# badge_0_0.net
KiCad netlist of a schematic drawn in EAGLE
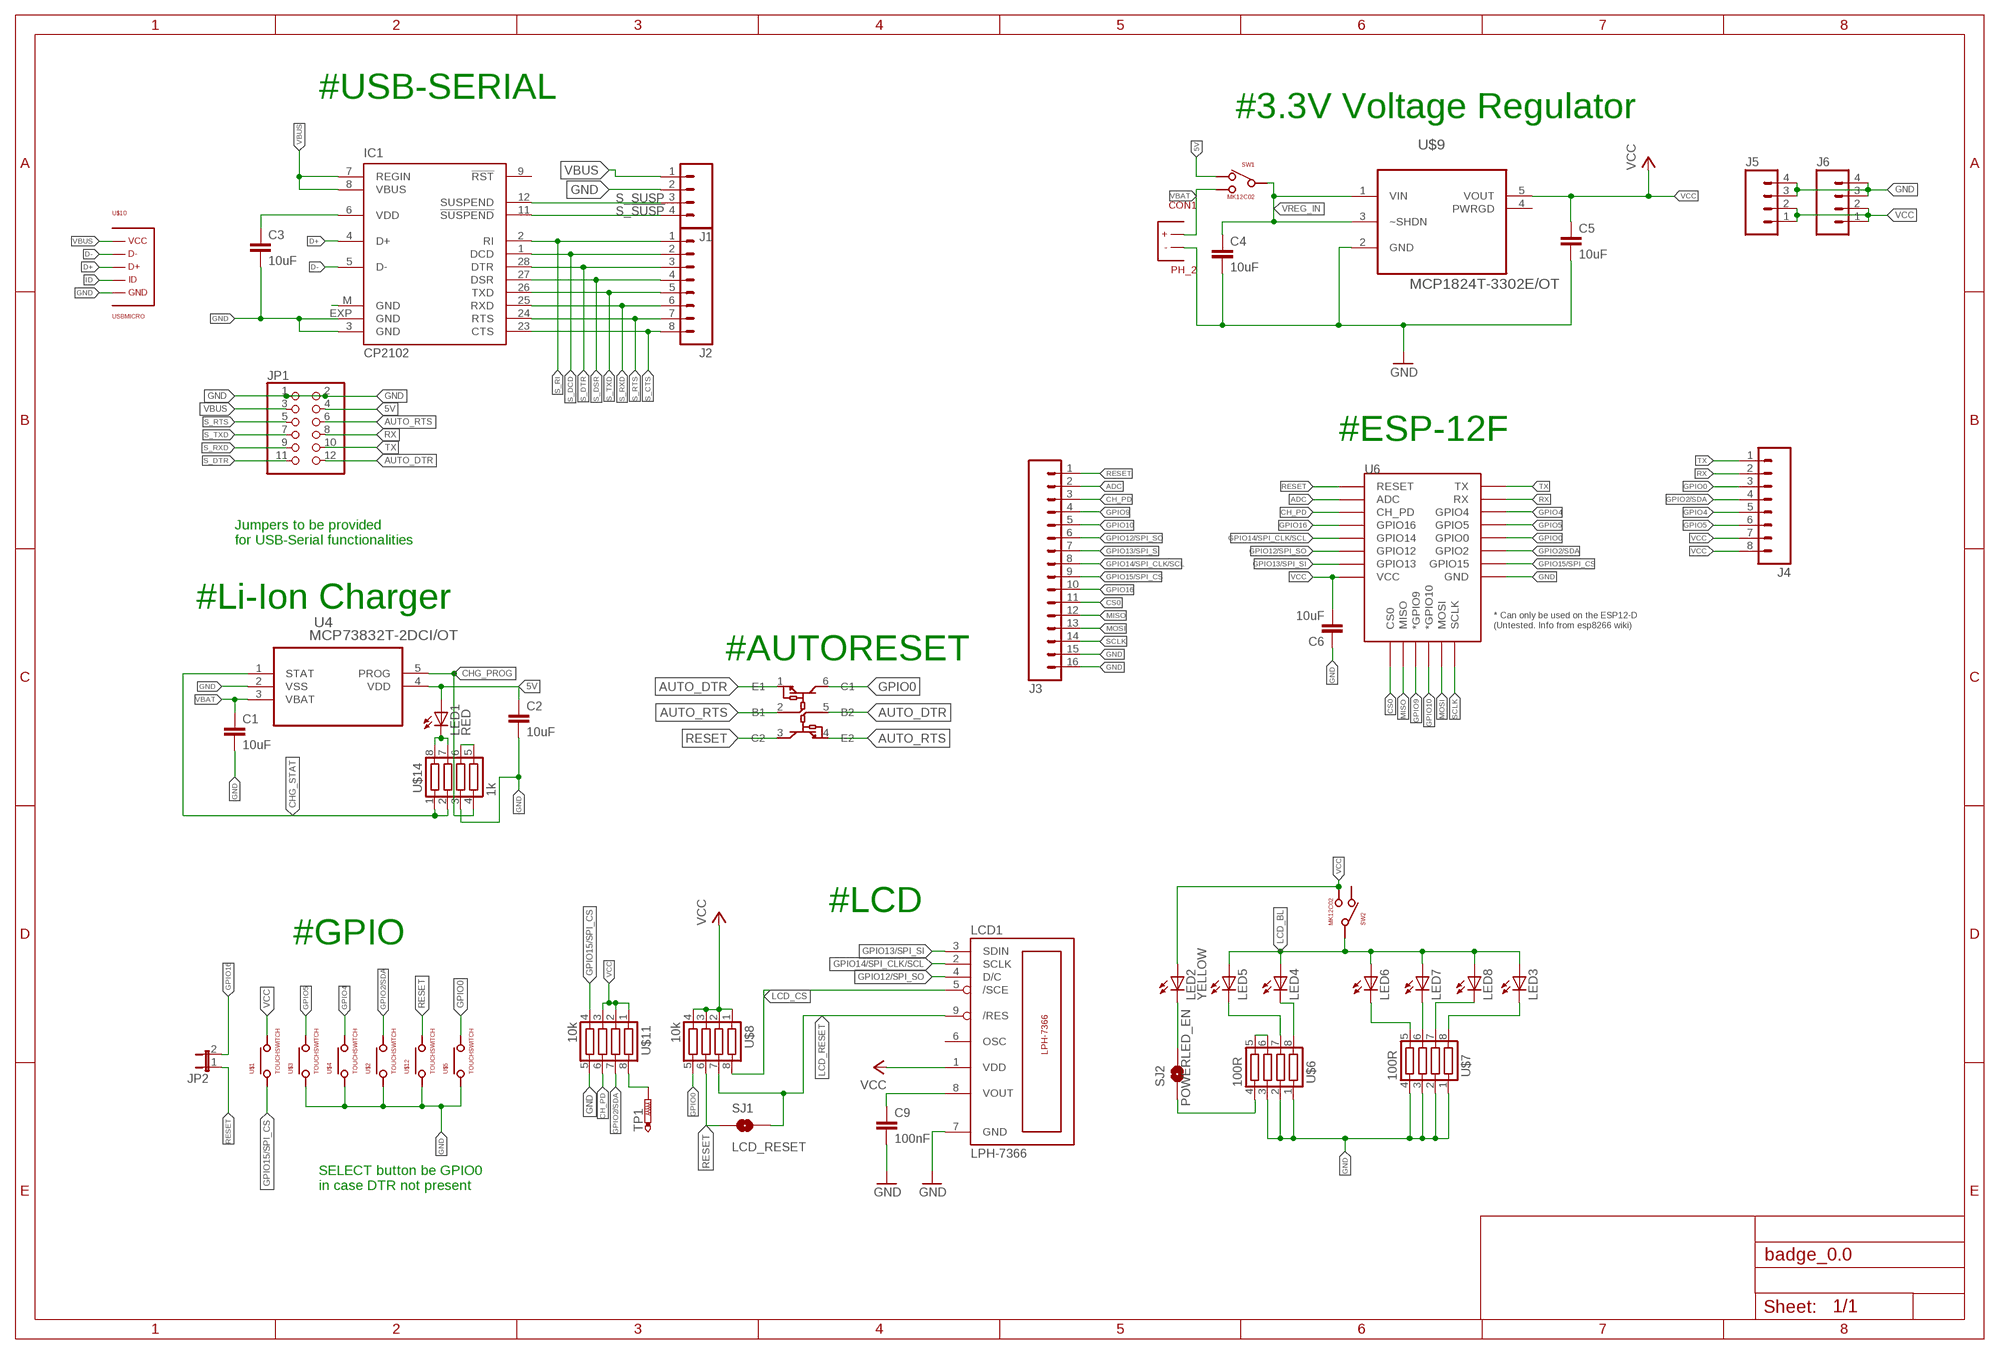
[diagram p0: schematic, sheet 1]

(export (version "E")
  (design (tool "Eeschema 10.0.6"))
  (components
    (comp (ref "C1")
      (value "10uF")
      (footprint "eagle-import:0805-CAP")
      (libsource (lib "eagle-import") (part "1UF-25V-10%(0805){dblquote}"))
    )
    (comp (ref "C2")
      (value "10uF")
      (footprint "eagle-import:0805-CAP")
      (libsource (lib "eagle-import") (part "1UF-25V-10%(0805){dblquote}"))
    )
    (comp (ref "C3")
      (value "10uF")
      (footprint "eagle-import:0805-CAP")
      (libsource (lib "eagle-import") (part "1UF-25V-10%(0805){dblquote}"))
    )
    (comp (ref "C4")
      (value "10uF")
      (footprint "eagle-import:0805-CAP")
      (libsource (lib "eagle-import") (part "1UF-25V-10%(0805){dblquote}"))
    )
    (comp (ref "C5")
      (value "10uF")
      (footprint "eagle-import:0805-CAP")
      (libsource (lib "eagle-import") (part "1UF-25V-10%(0805){dblquote}"))
    )
    (comp (ref "C6")
      (value "10uF")
      (footprint "eagle-import:0805-CAP")
      (libsource (lib "eagle-import") (part "1UF-25V-10%(0805){dblquote}"))
    )
    (comp (ref "C9")
      (value "100nF")
      (footprint "eagle-import:0805-CAP")
      (libsource (lib "eagle-import") (part "1UF-25V-10%(0805){dblquote}"))
    )
    (comp (ref "CON1")
      (value "PH_2")
      (footprint "eagle-import:PH_2")
      (libsource (lib "eagle-import") (part "PH_2"))
    )
    (comp (ref "IC1")
      (value "CP2102")
      (footprint "eagle-import:MLP28")
      (fields (field (name "MF") "FARNELL") (field (name "MPN") "CP2102-GM"))
      (libsource (lib "eagle-import") (part "CP2102"))
    )
    (comp (ref "J1")
      (value "M04PTH")
      (footprint "eagle-import:1X04")
      (libsource (lib "eagle-import") (part "M04PTH"))
    )
    (comp (ref "J2")
      (value "M08SILK_FEMALE_PTH")
      (footprint "eagle-import:1X08")
      (libsource (lib "eagle-import") (part "M08SILK_FEMALE_PTH"))
    )
    (comp (ref "J3")
      (value "M16PTH")
      (footprint "eagle-import:1X16")
      (libsource (lib "eagle-import") (part "M16PTH"))
    )
    (comp (ref "J4")
      (value "M08")
      (footprint "eagle-import:1X08_ROUND")
      (libsource (lib "eagle-import") (part "M08"))
    )
    (comp (ref "J5")
      (value "M04PTH")
      (footprint "eagle-import:1X04")
      (libsource (lib "eagle-import") (part "M04PTH"))
    )
    (comp (ref "J6")
      (value "M04PTH")
      (footprint "eagle-import:1X04")
      (libsource (lib "eagle-import") (part "M04PTH"))
    )
    (comp (ref "JP1")
      (value "PINHD-2X6")
      (footprint "eagle-import:2X06")
      (libsource (lib "eagle-import") (part "PINHD-2X6"))
    )
    (comp (ref "JP2")
      (value "JUMPER-2SMD-NO")
      (footprint "eagle-import:SJ_2S-NO")
      (libsource (lib "eagle-import") (part "JUMPER-2SMD-NO"))
    )
    (comp (ref "LCD1")
      (value "LPH-7366")
      (footprint "eagle-import:LPH-7366")
      (libsource (lib "eagle-import") (part "LPH-7366"))
    )
    (comp (ref "LED1")
      (value "RED")
      (footprint "eagle-import:SML0805")
      (libsource (lib "eagle-import") (part "LEDSML0805"))
    )
    (comp (ref "LED2")
      (value "YELLOW")
      (footprint "eagle-import:SML0805")
      (libsource (lib "eagle-import") (part "LEDSML0805"))
    )
    (comp (ref "LED3")
      (value "LEDSML0805")
      (footprint "eagle-import:SML0805")
      (libsource (lib "eagle-import") (part "LEDSML0805"))
    )
    (comp (ref "LED4")
      (value "LEDSML0805")
      (footprint "eagle-import:SML0805")
      (libsource (lib "eagle-import") (part "LEDSML0805"))
    )
    (comp (ref "LED5")
      (value "LEDSML0805")
      (footprint "eagle-import:SML0805")
      (libsource (lib "eagle-import") (part "LEDSML0805"))
    )
    (comp (ref "LED6")
      (value "LEDSML0805")
      (footprint "eagle-import:SML0805")
      (libsource (lib "eagle-import") (part "LEDSML0805"))
    )
    (comp (ref "LED7")
      (value "LEDSML0805")
      (footprint "eagle-import:SML0805")
      (libsource (lib "eagle-import") (part "LEDSML0805"))
    )
    (comp (ref "LED8")
      (value "LEDSML0805")
      (footprint "eagle-import:SML0805")
      (libsource (lib "eagle-import") (part "LEDSML0805"))
    )
    (comp (ref "SJ1")
      (value "LCD_RESET")
      (footprint "eagle-import:SJ_2S-TRACE")
      (libsource (lib "eagle-import") (part "SOLDERJUMPERTRACE"))
    )
    (comp (ref "SJ2")
      (value "POWERLED_EN")
      (footprint "eagle-import:SJ_2S-TRACE")
      (libsource (lib "eagle-import") (part "SOLDERJUMPERTRACE"))
    )
    (comp (ref "SW1")
      (value "MK12C02")
      (footprint "eagle-import:MK12C02")
      (libsource (lib "eagle-import") (part "MK12C02"))
    )
    (comp (ref "SW2")
      (value "MK12C02")
      (footprint "eagle-import:MK12C02")
      (libsource (lib "eagle-import") (part "MK12C02"))
    )
    (comp (ref "TP1")
      (value "PTR1B1,27")
      (footprint "eagle-import:B1,27")
      (libsource (lib "eagle-import") (part "PTR1B1,27"))
    )
    (comp (ref "U$1")
      (value "TOUCHSWITCH")
      (footprint "eagle-import:EVQQWN03W")
      (libsource (lib "eagle-import") (part "TOUCHSWITCH"))
    )
    (comp (ref "U$2")
      (value "TOUCHSWITCH")
      (footprint "eagle-import:EVQQWN03W")
      (libsource (lib "eagle-import") (part "TOUCHSWITCH"))
    )
    (comp (ref "U$3")
      (value "TOUCHSWITCH")
      (footprint "eagle-import:EVQQWN03W")
      (libsource (lib "eagle-import") (part "TOUCHSWITCH"))
    )
    (comp (ref "U$4")
      (value "TOUCHSWITCH")
      (footprint "eagle-import:EVQQWN03W")
      (libsource (lib "eagle-import") (part "TOUCHSWITCH"))
    )
    (comp (ref "U$5")
      (value "TOUCHSWITCH")
      (footprint "eagle-import:EVQQWN03W")
      (libsource (lib "eagle-import") (part "TOUCHSWITCH"))
    )
    (comp (ref "U$6")
      (value "100R")
      (footprint "eagle-import:YC164")
      (libsource (lib "eagle-import") (part "RES_ARR"))
    )
    (comp (ref "U$7")
      (value "100R")
      (footprint "eagle-import:YC164")
      (libsource (lib "eagle-import") (part "RES_ARR"))
    )
    (comp (ref "U$8")
      (value "10k")
      (footprint "eagle-import:YC164")
      (libsource (lib "eagle-import") (part "RES_ARR"))
    )
    (comp (ref "U$9")
      (value "MCP1824T-3302E/OT")
      (footprint "eagle-import:SOT95P270X145-5N")
      (libsource (lib "eagle-import") (part "MCP1824T-3302E/OT"))
    )
    (comp (ref "U$10")
      (value "USBMICRO")
      (footprint "eagle-import:USBMICRO")
      (libsource (lib "eagle-import") (part "USBMICRO"))
    )
    (comp (ref "U$11")
      (value "10k")
      (footprint "eagle-import:YC164")
      (libsource (lib "eagle-import") (part "RES_ARR"))
    )
    (comp (ref "U$12")
      (value "TOUCHSWITCH")
      (footprint "eagle-import:EVQQWN03W")
      (libsource (lib "eagle-import") (part "TOUCHSWITCH"))
    )
    (comp (ref "U$13")
      (value "PEMH9,115")
      (footprint "eagle-import:SOT666")
      (libsource (lib "eagle-import") (part "PEMH9,115"))
    )
    (comp (ref "U$14")
      (value "1k")
      (footprint "eagle-import:YC164")
      (libsource (lib "eagle-import") (part "RES_ARR"))
    )
    (comp (ref "U4")
      (value "MCP73832T-2DCI/OT")
      (footprint "eagle-import:SOT95P300X145-5N")
      (libsource (lib "eagle-import") (part "MCP73832T-2DCI/OT"))
    )
    (comp (ref "U6")
      (value "ESP12ESMD")
      (footprint "eagle-import:ESP12E-SMD")
      (libsource (lib "eagle-import") (part "ESP12ESMD"))
    )
  )
  (nets
    (net (code "1") (name "/S_SUSP") (class "Default")
      (node (ref "IC1") (pin "12") (pinfunction "SUSPEND_12") (pintype "output"))
      (node (ref "J1") (pin "3") (pinfunction "3_3") (pintype "passive"))
    )
    (net (code "2") (name "/S_~{SUSP}") (class "Default")
      (node (ref "IC1") (pin "11") (pinfunction "~{SUSPEND}_11") (pintype "output"))
      (node (ref "J1") (pin "4") (pinfunction "4_4") (pintype "passive"))
    )
    (net (code "3") (name "5V") (class "Default")
      (node (ref "C2") (pin "1") (pinfunction "1_1") (pintype "passive"))
      (node (ref "JP1") (pin "4") (pinfunction "4_4") (pintype "passive"))
      (node (ref "LED1") (pin "A") (pinfunction "A_A") (pintype "passive"))
      (node (ref "SW1") (pin "P$2") (pinfunction "P$2_P$2") (pintype "bidirectional"))
      (node (ref "U4") (pin "4") (pinfunction "VDD_4") (pintype "power_in"))
    )
    (net (code "4") (name "ADC") (class "Default")
      (node (ref "J3") (pin "2") (pinfunction "2_2") (pintype "passive"))
      (node (ref "U6") (pin "ADC") (pinfunction "ADC_ADC") (pintype "bidirectional"))
    )
    (net (code "5") (name "AUTO_DTR") (class "Default")
      (node (ref "JP1") (pin "12") (pinfunction "12_12") (pintype "passive"))
      (node (ref "U$13") (pin "1") (pinfunction "E1_1") (pintype "bidirectional"))
      (node (ref "U$13") (pin "5") (pinfunction "B2_5") (pintype "bidirectional"))
    )
    (net (code "6") (name "AUTO_RTS") (class "Default")
      (node (ref "JP1") (pin "6") (pinfunction "6_6") (pintype "passive"))
      (node (ref "U$13") (pin "2") (pinfunction "B1_2") (pintype "bidirectional"))
      (node (ref "U$13") (pin "4") (pinfunction "E2_4") (pintype "bidirectional"))
    )
    (net (code "7") (name "CHG_PROG") (class "Default")
      (node (ref "U$14") (pin "4") (pinfunction "4_4") (pintype "passive"))
      (node (ref "U4") (pin "5") (pinfunction "PROG_5") (pintype "input"))
    )
    (net (code "8") (name "CHG_STAT") (class "Default")
      (node (ref "U$14") (pin "1") (pinfunction "1_1") (pintype "passive"))
      (node (ref "U$14") (pin "2") (pinfunction "2_2") (pintype "passive"))
      (node (ref "U4") (pin "1") (pinfunction "STAT_1") (pintype "input"))
    )
    (net (code "9") (name "CH_PD") (class "Default")
      (node (ref "J3") (pin "3") (pinfunction "3_3") (pintype "passive"))
      (node (ref "U$11") (pin "6") (pinfunction "6_6") (pintype "passive"))
      (node (ref "U6") (pin "CH_PD") (pinfunction "CH_PD_CH_PD") (pintype "bidirectional"))
    )
    (net (code "10") (name "CS0") (class "Default")
      (node (ref "J3") (pin "11") (pinfunction "11_11") (pintype "passive"))
      (node (ref "U6") (pin "CS0") (pinfunction "CS0_CS0") (pintype "bidirectional"))
    )
    (net (code "11") (name "D+") (class "Default")
      (node (ref "IC1") (pin "4") (pinfunction "D+_4") (pintype "bidirectional"))
      (node (ref "U$10") (pin "P$D+") (pinfunction "P$D+_P$D+") (pintype "bidirectional"))
    )
    (net (code "12") (name "D-") (class "Default")
      (node (ref "IC1") (pin "5") (pinfunction "D-_5") (pintype "bidirectional"))
      (node (ref "U$10") (pin "P$D-") (pinfunction "P$D-_P$D-") (pintype "bidirectional"))
    )
    (net (code "13") (name "GND") (class "Default")
      (node (ref "C1") (pin "2") (pinfunction "2_2") (pintype "passive"))
      (node (ref "C2") (pin "2") (pinfunction "2_2") (pintype "passive"))
      (node (ref "C3") (pin "2") (pinfunction "2_2") (pintype "passive"))
      (node (ref "C4") (pin "2") (pinfunction "2_2") (pintype "passive"))
      (node (ref "C5") (pin "2") (pinfunction "2_2") (pintype "passive"))
      (node (ref "C6") (pin "1") (pinfunction "1_1") (pintype "passive"))
      (node (ref "C9") (pin "2") (pinfunction "2_2") (pintype "passive"))
      (node (ref "CON1") (pin "P$1") (pinfunction "P$2_P$1") (pintype "bidirectional"))
      (node (ref "IC1") (pin "3") (pinfunction "GND_3") (pintype "power_in"))
      (node (ref "IC1") (pin "EXP") (pinfunction "GND_EXP") (pintype "power_in"))
      (node (ref "J1") (pin "2") (pinfunction "2_2") (pintype "passive"))
      (node (ref "J3") (pin "15") (pinfunction "15_15") (pintype "passive"))
      (node (ref "J3") (pin "16") (pinfunction "16_16") (pintype "passive"))
      (node (ref "J5") (pin "3") (pinfunction "3_3") (pintype "passive"))
      (node (ref "J5") (pin "4") (pinfunction "4_4") (pintype "passive"))
      (node (ref "J6") (pin "3") (pinfunction "3_3") (pintype "passive"))
      (node (ref "J6") (pin "4") (pinfunction "4_4") (pintype "passive"))
      (node (ref "JP1") (pin "1") (pinfunction "1_1") (pintype "passive"))
      (node (ref "JP1") (pin "2") (pinfunction "2_2") (pintype "passive"))
      (node (ref "LCD1") (pin "7") (pinfunction "GND_7") (pintype "power_in"))
      (node (ref "U$10") (pin "P$GND") (pinfunction "P$GND_P$GND") (pintype "bidirectional"))
      (node (ref "U$11") (pin "5") (pinfunction "5_5") (pintype "passive"))
      (node (ref "U$12") (pin "P$1") (pinfunction "P$1_P$1") (pintype "bidirectional"))
      (node (ref "U$12") (pin "P$4") (pinfunction "P$1_P$4") (pintype "bidirectional"))
      (node (ref "U$14") (pin "3") (pinfunction "3_3") (pintype "passive"))
      (node (ref "U$2") (pin "P$1") (pinfunction "P$1_P$1") (pintype "bidirectional"))
      (node (ref "U$2") (pin "P$4") (pinfunction "P$1_P$4") (pintype "bidirectional"))
      (node (ref "U$3") (pin "P$1") (pinfunction "P$1_P$1") (pintype "bidirectional"))
      (node (ref "U$3") (pin "P$4") (pinfunction "P$1_P$4") (pintype "bidirectional"))
      (node (ref "U$4") (pin "P$1") (pinfunction "P$1_P$1") (pintype "bidirectional"))
      (node (ref "U$4") (pin "P$4") (pinfunction "P$1_P$4") (pintype "bidirectional"))
      (node (ref "U$5") (pin "P$1") (pinfunction "P$1_P$1") (pintype "bidirectional"))
      (node (ref "U$5") (pin "P$4") (pinfunction "P$1_P$4") (pintype "bidirectional"))
      (node (ref "U$6") (pin "1") (pinfunction "1_1") (pintype "passive"))
      (node (ref "U$6") (pin "2") (pinfunction "2_2") (pintype "passive"))
      (node (ref "U$6") (pin "3") (pinfunction "3_3") (pintype "passive"))
      (node (ref "U$7") (pin "1") (pinfunction "1_1") (pintype "passive"))
      (node (ref "U$7") (pin "2") (pinfunction "2_2") (pintype "passive"))
      (node (ref "U$7") (pin "3") (pinfunction "3_3") (pintype "passive"))
      (node (ref "U$7") (pin "4") (pinfunction "4_4") (pintype "passive"))
      (node (ref "U$9") (pin "2") (pinfunction "GND_2") (pintype "passive"))
      (node (ref "U4") (pin "2") (pinfunction "VSS_2") (pintype "passive"))
      (node (ref "U6") (pin "GND") (pinfunction "GND_GND") (pintype "bidirectional"))
    )
    (net (code "14") (name "GPIO0") (class "Default")
      (node (ref "J4") (pin "3") (pinfunction "3_3") (pintype "passive"))
      (node (ref "U$13") (pin "6") (pinfunction "C1_6") (pintype "bidirectional"))
      (node (ref "U$5") (pin "P$2") (pinfunction "P$2_P$2") (pintype "bidirectional"))
      (node (ref "U$5") (pin "P$3") (pinfunction "P$2_P$3") (pintype "bidirectional"))
      (node (ref "U$8") (pin "5") (pinfunction "5_5") (pintype "passive"))
      (node (ref "U6") (pin "GPIO0") (pinfunction "GPIO0_GPIO0") (pintype "bidirectional"))
    )
    (net (code "15") (name "GPIO2{slash}SDA") (class "Default")
      (node (ref "J4") (pin "4") (pinfunction "4_4") (pintype "passive"))
      (node (ref "U$11") (pin "7") (pinfunction "7_7") (pintype "passive"))
      (node (ref "U$2") (pin "P$2") (pinfunction "P$2_P$2") (pintype "bidirectional"))
      (node (ref "U$2") (pin "P$3") (pinfunction "P$2_P$3") (pintype "bidirectional"))
      (node (ref "U6") (pin "GPIO2") (pinfunction "GPIO2_GPIO2") (pintype "bidirectional"))
    )
    (net (code "16") (name "GPIO4") (class "Default")
      (node (ref "J4") (pin "5") (pinfunction "5_5") (pintype "passive"))
      (node (ref "U$4") (pin "P$2") (pinfunction "P$2_P$2") (pintype "bidirectional"))
      (node (ref "U$4") (pin "P$3") (pinfunction "P$2_P$3") (pintype "bidirectional"))
      (node (ref "U6") (pin "GPIO4") (pinfunction "GPIO4_GPIO4") (pintype "bidirectional"))
    )
    (net (code "17") (name "GPIO5") (class "Default")
      (node (ref "J4") (pin "6") (pinfunction "6_6") (pintype "passive"))
      (node (ref "U$3") (pin "P$2") (pinfunction "P$2_P$2") (pintype "bidirectional"))
      (node (ref "U$3") (pin "P$3") (pinfunction "P$2_P$3") (pintype "bidirectional"))
      (node (ref "U6") (pin "GPIO5") (pinfunction "GPIO5_GPIO5") (pintype "bidirectional"))
    )
    (net (code "18") (name "GPIO9") (class "Default")
      (node (ref "J3") (pin "4") (pinfunction "4_4") (pintype "passive"))
      (node (ref "U6") (pin "GPIO9") (pinfunction "*GPIO9_GPIO9") (pintype "bidirectional"))
    )
    (net (code "19") (name "GPIO10") (class "Default")
      (node (ref "J3") (pin "5") (pinfunction "5_5") (pintype "passive"))
      (node (ref "U6") (pin "GPIO10") (pinfunction "*GPIO10_GPIO10") (pintype "bidirectional"))
    )
    (net (code "20") (name "GPIO12{slash}SPI_SO") (class "Default")
      (node (ref "J3") (pin "6") (pinfunction "6_6") (pintype "passive"))
      (node (ref "LCD1") (pin "4") (pinfunction "D/C_4") (pintype "input"))
      (node (ref "U6") (pin "GPIO12") (pinfunction "GPIO12_GPIO12") (pintype "bidirectional"))
    )
    (net (code "21") (name "GPIO13{slash}SPI_SI") (class "Default")
      (node (ref "J3") (pin "7") (pinfunction "7_7") (pintype "passive"))
      (node (ref "LCD1") (pin "3") (pinfunction "SDIN_3") (pintype "input"))
      (node (ref "U6") (pin "GPIO13") (pinfunction "GPIO13_GPIO13") (pintype "bidirectional"))
    )
    (net (code "22") (name "GPIO14{slash}SPI_CLK{slash}SCL") (class "Default")
      (node (ref "J3") (pin "8") (pinfunction "8_8") (pintype "passive"))
      (node (ref "LCD1") (pin "2") (pinfunction "SCLK_2") (pintype "input"))
      (node (ref "U6") (pin "GPIO14") (pinfunction "GPIO14_GPIO14") (pintype "bidirectional"))
    )
    (net (code "23") (name "GPIO15{slash}SPI_CS") (class "Default")
      (node (ref "J3") (pin "9") (pinfunction "9_9") (pintype "passive"))
      (node (ref "U$1") (pin "P$1") (pinfunction "P$1_P$1") (pintype "bidirectional"))
      (node (ref "U$1") (pin "P$4") (pinfunction "P$1_P$4") (pintype "bidirectional"))
      (node (ref "U$11") (pin "4") (pinfunction "4_4") (pintype "passive"))
      (node (ref "U6") (pin "GPIO15") (pinfunction "GPIO15_GPIO15") (pintype "bidirectional"))
    )
    (net (code "24") (name "GPIO16") (class "Default")
      (node (ref "J3") (pin "10") (pinfunction "10_10") (pintype "passive"))
      (node (ref "JP2") (pin "2") (pinfunction "2_2") (pintype "passive"))
      (node (ref "U6") (pin "GPIO16") (pinfunction "GPIO16_GPIO16") (pintype "bidirectional"))
    )
    (net (code "25") (name "ID") (class "Default")
      (node (ref "U$10") (pin "P$ID") (pinfunction "P$ID_P$ID") (pintype "bidirectional"))
    )
    (net (code "26") (name "LCD_BL") (class "Default")
      (node (ref "LED3") (pin "A") (pinfunction "A_A") (pintype "passive"))
      (node (ref "LED4") (pin "A") (pinfunction "A_A") (pintype "passive"))
      (node (ref "LED5") (pin "A") (pinfunction "A_A") (pintype "passive"))
      (node (ref "LED6") (pin "A") (pinfunction "A_A") (pintype "passive"))
      (node (ref "LED7") (pin "A") (pinfunction "A_A") (pintype "passive"))
      (node (ref "LED8") (pin "A") (pinfunction "A_A") (pintype "passive"))
      (node (ref "SW2") (pin "P$1") (pinfunction "P$1_P$1") (pintype "bidirectional"))
    )
    (net (code "27") (name "LCD_CS") (class "Default")
      (node (ref "LCD1") (pin "5") (pinfunction "/SCE_5") (pintype "input"))
      (node (ref "U$8") (pin "8") (pinfunction "8_8") (pintype "passive"))
    )
    (net (code "28") (name "LCD_RESET") (class "Default")
      (node (ref "LCD1") (pin "9") (pinfunction "/RES_9") (pintype "input"))
      (node (ref "SJ1") (pin "2") (pinfunction "2_2") (pintype "passive"))
      (node (ref "U$8") (pin "7") (pinfunction "7_7") (pintype "passive"))
    )
    (net (code "29") (name "MISO") (class "Default")
      (node (ref "J3") (pin "12") (pinfunction "12_12") (pintype "passive"))
      (node (ref "U6") (pin "MISO") (pinfunction "MISO_MISO") (pintype "bidirectional"))
    )
    (net (code "30") (name "MOSI") (class "Default")
      (node (ref "J3") (pin "13") (pinfunction "13_13") (pintype "passive"))
      (node (ref "U6") (pin "MOSI") (pinfunction "MOSI_MOSI") (pintype "bidirectional"))
    )
    (net (code "31") (name "Net-(IC1-VDD)") (class "Default")
      (node (ref "C3") (pin "1") (pinfunction "1_1") (pintype "passive"))
      (node (ref "IC1") (pin "6") (pinfunction "VDD_6") (pintype "power_in"))
    )
    (net (code "32") (name "Net-(LCD1-VOUT)") (class "Default")
      (node (ref "C9") (pin "1") (pinfunction "1_1") (pintype "passive"))
      (node (ref "LCD1") (pin "8") (pinfunction "VOUT_8") (pintype "passive"))
    )
    (net (code "33") (name "Net-(LED1-PadC)") (class "Default")
      (node (ref "LED1") (pin "C") (pinfunction "C_C") (pintype "passive"))
      (node (ref "U$14") (pin "7") (pinfunction "7_7") (pintype "passive"))
      (node (ref "U$14") (pin "8") (pinfunction "8_8") (pintype "passive"))
    )
    (net (code "34") (name "Net-(LED2-PadC)") (class "Default")
      (node (ref "LED2") (pin "C") (pinfunction "C_C") (pintype "passive"))
      (node (ref "SJ2") (pin "2") (pinfunction "2_2") (pintype "passive"))
    )
    (net (code "35") (name "Net-(LED3-PadC)") (class "Default")
      (node (ref "LED3") (pin "C") (pinfunction "C_C") (pintype "passive"))
      (node (ref "U$7") (pin "8") (pinfunction "8_8") (pintype "passive"))
    )
    (net (code "36") (name "Net-(LED4-PadC)") (class "Default")
      (node (ref "LED4") (pin "C") (pinfunction "C_C") (pintype "passive"))
      (node (ref "U$6") (pin "8") (pinfunction "8_8") (pintype "passive"))
    )
    (net (code "37") (name "Net-(LED5-PadC)") (class "Default")
      (node (ref "LED5") (pin "C") (pinfunction "C_C") (pintype "passive"))
      (node (ref "U$6") (pin "7") (pinfunction "7_7") (pintype "passive"))
    )
    (net (code "38") (name "Net-(LED6-PadC)") (class "Default")
      (node (ref "LED6") (pin "C") (pinfunction "C_C") (pintype "passive"))
      (node (ref "U$7") (pin "5") (pinfunction "5_5") (pintype "passive"))
    )
    (net (code "39") (name "Net-(LED7-PadC)") (class "Default")
      (node (ref "LED7") (pin "C") (pinfunction "C_C") (pintype "passive"))
      (node (ref "U$7") (pin "6") (pinfunction "6_6") (pintype "passive"))
    )
    (net (code "40") (name "Net-(LED8-PadC)") (class "Default")
      (node (ref "LED8") (pin "C") (pinfunction "C_C") (pintype "passive"))
      (node (ref "U$7") (pin "7") (pinfunction "7_7") (pintype "passive"))
    )
    (net (code "41") (name "Net-(SJ2-Pad1)") (class "Default")
      (node (ref "SJ2") (pin "1") (pinfunction "1_1") (pintype "passive"))
      (node (ref "U$6") (pin "4") (pinfunction "4_4") (pintype "passive"))
    )
    (net (code "42") (name "Net-(TP1-PadTP)") (class "Default")
      (node (ref "TP1") (pin "TP") (pinfunction "TP_TP") (pintype "input"))
      (node (ref "U$11") (pin "8") (pinfunction "8_8") (pintype "passive"))
    )
    (net (code "43") (name "Net-(U$6-Pad5)") (class "Default")
      (node (ref "U$6") (pin "5") (pinfunction "5_5") (pintype "passive"))
      (node (ref "U$6") (pin "6") (pinfunction "6_6") (pintype "passive"))
    )
    (net (code "44") (name "Net-(U$14-Pad5)") (class "Default")
      (node (ref "U$14") (pin "5") (pinfunction "5_5") (pintype "passive"))
      (node (ref "U$14") (pin "6") (pinfunction "6_6") (pintype "passive"))
    )
    (net (code "45") (name "RESET") (class "Default")
      (node (ref "J3") (pin "1") (pinfunction "1_1") (pintype "passive"))
      (node (ref "JP2") (pin "1") (pinfunction "1_1") (pintype "passive"))
      (node (ref "SJ1") (pin "1") (pinfunction "1_1") (pintype "passive"))
      (node (ref "U$12") (pin "P$2") (pinfunction "P$2_P$2") (pintype "bidirectional"))
      (node (ref "U$12") (pin "P$3") (pinfunction "P$2_P$3") (pintype "bidirectional"))
      (node (ref "U$13") (pin "3") (pinfunction "C2_3") (pintype "bidirectional"))
      (node (ref "U$8") (pin "6") (pinfunction "6_6") (pintype "passive"))
      (node (ref "U6") (pin "RESET") (pinfunction "RESET_RESET") (pintype "bidirectional"))
    )
    (net (code "46") (name "RX") (class "Default")
      (node (ref "J4") (pin "2") (pinfunction "2_2") (pintype "passive"))
      (node (ref "JP1") (pin "8") (pinfunction "8_8") (pintype "passive"))
      (node (ref "U6") (pin "RXD0") (pinfunction "RX_RXD0") (pintype "bidirectional"))
    )
    (net (code "47") (name "SCLK") (class "Default")
      (node (ref "J3") (pin "14") (pinfunction "14_14") (pintype "passive"))
      (node (ref "U6") (pin "SCLK") (pinfunction "SCLK_SCLK") (pintype "bidirectional"))
    )
    (net (code "48") (name "S_CTS") (class "Default")
      (node (ref "IC1") (pin "23") (pinfunction "CTS_23") (pintype "input"))
      (node (ref "J2") (pin "8") (pinfunction "8_8") (pintype "passive"))
    )
    (net (code "49") (name "S_DCD") (class "Default")
      (node (ref "IC1") (pin "1") (pinfunction "DCD_1") (pintype "input"))
      (node (ref "J2") (pin "2") (pinfunction "2_2") (pintype "passive"))
    )
    (net (code "50") (name "S_DSR") (class "Default")
      (node (ref "IC1") (pin "27") (pinfunction "DSR_27") (pintype "input"))
      (node (ref "J2") (pin "4") (pinfunction "4_4") (pintype "passive"))
    )
    (net (code "51") (name "S_DTR") (class "Default")
      (node (ref "IC1") (pin "28") (pinfunction "DTR_28") (pintype "output"))
      (node (ref "J2") (pin "3") (pinfunction "3_3") (pintype "passive"))
      (node (ref "JP1") (pin "11") (pinfunction "11_11") (pintype "passive"))
    )
    (net (code "52") (name "S_RI") (class "Default")
      (node (ref "IC1") (pin "2") (pinfunction "RI_2") (pintype "input"))
      (node (ref "J2") (pin "1") (pinfunction "1_1") (pintype "passive"))
    )
    (net (code "53") (name "S_RTS") (class "Default")
      (node (ref "IC1") (pin "24") (pinfunction "RTS_24") (pintype "output"))
      (node (ref "J2") (pin "7") (pinfunction "7_7") (pintype "passive"))
      (node (ref "JP1") (pin "5") (pinfunction "5_5") (pintype "passive"))
    )
    (net (code "54") (name "S_RXD") (class "Default")
      (node (ref "IC1") (pin "25") (pinfunction "RXD_25") (pintype "input"))
      (node (ref "J2") (pin "6") (pinfunction "6_6") (pintype "passive"))
      (node (ref "JP1") (pin "9") (pinfunction "9_9") (pintype "passive"))
    )
    (net (code "55") (name "S_TXD") (class "Default")
      (node (ref "IC1") (pin "26") (pinfunction "TXD_26") (pintype "output"))
      (node (ref "J2") (pin "5") (pinfunction "5_5") (pintype "passive"))
      (node (ref "JP1") (pin "7") (pinfunction "7_7") (pintype "passive"))
    )
    (net (code "56") (name "TX") (class "Default")
      (node (ref "J4") (pin "1") (pinfunction "1_1") (pintype "passive"))
      (node (ref "JP1") (pin "10") (pinfunction "10_10") (pintype "passive"))
      (node (ref "U6") (pin "TXD0") (pinfunction "TX_TXD0") (pintype "bidirectional"))
    )
    (net (code "57") (name "VBAT") (class "Default")
      (node (ref "C1") (pin "1") (pinfunction "1_1") (pintype "passive"))
      (node (ref "CON1") (pin "P$2") (pinfunction "P$1_P$2") (pintype "bidirectional"))
      (node (ref "SW1") (pin "P$3") (pinfunction "P$3_P$3") (pintype "bidirectional"))
      (node (ref "U4") (pin "3") (pinfunction "VBAT_3") (pintype "input"))
    )
    (net (code "58") (name "VBUS") (class "Default")
      (node (ref "IC1") (pin "7") (pinfunction "REGIN_7") (pintype "passive"))
      (node (ref "IC1") (pin "8") (pinfunction "VBUS_8") (pintype "input"))
      (node (ref "J1") (pin "1") (pinfunction "1_1") (pintype "passive"))
      (node (ref "JP1") (pin "3") (pinfunction "3_3") (pintype "passive"))
      (node (ref "U$10") (pin "P$VCC") (pinfunction "P$VCC_P$VCC") (pintype "bidirectional"))
    )
    (net (code "59") (name "VCC") (class "Default")
      (node (ref "C5") (pin "1") (pinfunction "1_1") (pintype "passive"))
      (node (ref "C6") (pin "2") (pinfunction "2_2") (pintype "passive"))
      (node (ref "J4") (pin "7") (pinfunction "7_7") (pintype "passive"))
      (node (ref "J4") (pin "8") (pinfunction "8_8") (pintype "passive"))
      (node (ref "J5") (pin "1") (pinfunction "1_1") (pintype "passive"))
      (node (ref "J5") (pin "2") (pinfunction "2_2") (pintype "passive"))
      (node (ref "J6") (pin "1") (pinfunction "1_1") (pintype "passive"))
      (node (ref "J6") (pin "2") (pinfunction "2_2") (pintype "passive"))
      (node (ref "LCD1") (pin "1") (pinfunction "VDD_1") (pintype "power_in"))
      (node (ref "LED2") (pin "A") (pinfunction "A_A") (pintype "passive"))
      (node (ref "SW2") (pin "P$3") (pinfunction "P$3_P$3") (pintype "bidirectional"))
      (node (ref "U$1") (pin "P$2") (pinfunction "P$2_P$2") (pintype "bidirectional"))
      (node (ref "U$1") (pin "P$3") (pinfunction "P$2_P$3") (pintype "bidirectional"))
      (node (ref "U$11") (pin "1") (pinfunction "1_1") (pintype "passive"))
      (node (ref "U$11") (pin "2") (pinfunction "2_2") (pintype "passive"))
      (node (ref "U$11") (pin "3") (pinfunction "3_3") (pintype "passive"))
      (node (ref "U$8") (pin "1") (pinfunction "1_1") (pintype "passive"))
      (node (ref "U$8") (pin "2") (pinfunction "2_2") (pintype "passive"))
      (node (ref "U$8") (pin "3") (pinfunction "3_3") (pintype "passive"))
      (node (ref "U$8") (pin "4") (pinfunction "4_4") (pintype "passive"))
      (node (ref "U$9") (pin "5") (pinfunction "VOUT_5") (pintype "output"))
      (node (ref "U6") (pin "VCC") (pinfunction "VCC_VCC") (pintype "bidirectional"))
    )
    (net (code "60") (name "VREG_IN") (class "Default")
      (node (ref "C4") (pin "1") (pinfunction "1_1") (pintype "passive"))
      (node (ref "SW1") (pin "P$1") (pinfunction "P$1_P$1") (pintype "bidirectional"))
      (node (ref "U$9") (pin "1") (pinfunction "VIN_1") (pintype "input"))
      (node (ref "U$9") (pin "3") (pinfunction "~{SHDN}_3") (pintype "input"))
    )
    (net (code "61") (name "unconnected-(IC1-GND-PadM)") (class "Default")
      (node (ref "IC1") (pin "M") (pinfunction "GND_M") (pintype "power_in"))
    )
    (net (code "62") (name "unconnected-(IC1-~{RST}-Pad9)") (class "Default")
      (node (ref "IC1") (pin "9") (pinfunction "~{RST}_9") (pintype "bidirectional"))
    )
    (net (code "63") (name "unconnected-(LCD1-OSC-Pad6)") (class "Default")
      (node (ref "LCD1") (pin "6") (pinfunction "OSC_6") (pintype "passive"))
    )
    (net (code "64") (name "unconnected-(SW2-PadP$2)") (class "Default")
      (node (ref "SW2") (pin "P$2") (pinfunction "P$2_P$2") (pintype "bidirectional"))
    )
    (net (code "65") (name "unconnected-(U$9-PWRGD-Pad4)") (class "Default")
      (node (ref "U$9") (pin "4") (pinfunction "PWRGD_4") (pintype "output"))
    )
  )
)
